# zero-o2-eliminator.net
KiCad netlist of a schematic drawn in EAGLE
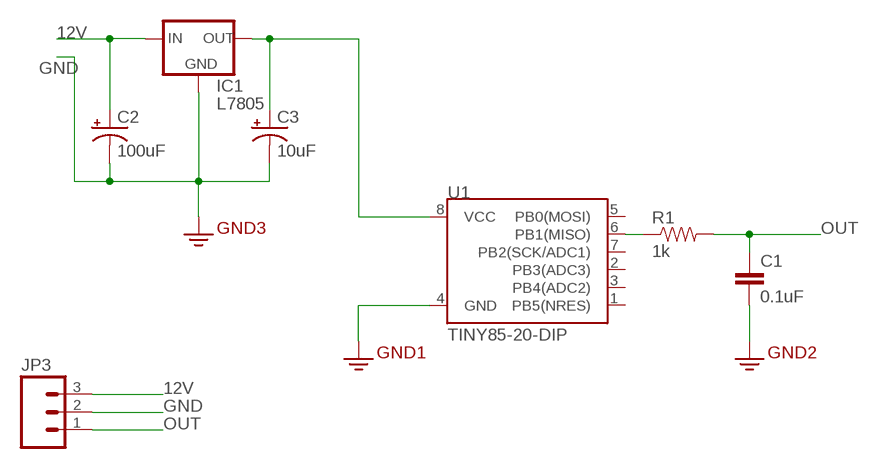
[diagram p0: schematic, sheet 1]

(export (version "E")
  (design (tool "Eeschema 10.0.6"))
  (components
    (comp (ref "C1")
      (value "0.1uF")
      (footprint "eagle-import:CAP-PTH-SMALL-KIT")
      (libsource (lib "eagle-import") (part "0.1UF-50V-20%(PTH)KIT-EZ"))
    )
    (comp (ref "C2")
      (value "100uF")
      (footprint "eagle-import:CPOL-RADIAL-10UF-25V-KIT")
      (libsource (lib "eagle-import") (part "10UF-25V-20%(PTH)KIT"))
    )
    (comp (ref "C3")
      (value "10uF")
      (footprint "eagle-import:CPOL-RADIAL-10UF-25V-KIT")
      (libsource (lib "eagle-import") (part "10UF-25V-20%(PTH)KIT"))
    )
    (comp (ref "IC1")
      (value "L7805")
      (footprint "eagle-import:78XXL")
      (libsource (lib "eagle-import") (part "V_REG_78XXSIDE"))
    )
    (comp (ref "JP3")
      (value "M03SCREW")
      (footprint "eagle-import:SCREWTERMINAL-3.5MM-3")
      (libsource (lib "eagle-import") (part "M03SCREW"))
    )
    (comp (ref "R1")
      (value "1k")
      (footprint "eagle-import:AXIAL-0.1EZ")
      (libsource (lib "eagle-import") (part "1KOHM-1/4W-5%(PTH)VERT-KIT"))
    )
    (comp (ref "U1")
      (value "TINY85-20-DIP")
      (footprint "eagle-import:DIP08")
      (libsource (lib "eagle-import") (part "ATTINY45TINY85-20-DIP"))
    )
  )
  (nets
    (net (code "1") (name "/12V") (class "Default")
      (node (ref "C2") (pin "1") (pinfunction "+_1") (pintype "passive"))
      (node (ref "IC1") (pin "IN") (pinfunction "IN_IN") (pintype "input"))
      (node (ref "JP3") (pin "3") (pinfunction "3_3") (pintype "passive"))
    )
    (net (code "2") (name "/OUT") (class "Default")
      (node (ref "C1") (pin "1") (pinfunction "1_1") (pintype "passive"))
      (node (ref "JP3") (pin "1") (pinfunction "1_1") (pintype "passive"))
      (node (ref "R1") (pin "P$2") (pinfunction "2_P$2") (pintype "passive"))
    )
    (net (code "3") (name "GND2") (class "Default")
      (node (ref "C1") (pin "2") (pinfunction "2_2") (pintype "passive"))
      (node (ref "C2") (pin "2") (pinfunction "-_2") (pintype "passive"))
      (node (ref "C3") (pin "2") (pinfunction "-_2") (pintype "passive"))
      (node (ref "IC1") (pin "GND") (pinfunction "GND_GND") (pintype "input"))
      (node (ref "JP3") (pin "2") (pinfunction "2_2") (pintype "passive"))
      (node (ref "U1") (pin "4") (pinfunction "GND_4") (pintype "bidirectional"))
    )
    (net (code "4") (name "Net-(C3-+)") (class "Default")
      (node (ref "C3") (pin "1") (pinfunction "+_1") (pintype "passive"))
      (node (ref "IC1") (pin "OUT") (pinfunction "OUT_OUT") (pintype "output"))
      (node (ref "U1") (pin "8") (pinfunction "VCC_8") (pintype "bidirectional"))
    )
    (net (code "5") (name "Net-(R1-1)") (class "Default")
      (node (ref "R1") (pin "P$1") (pinfunction "1_P$1") (pintype "passive"))
      (node (ref "U1") (pin "6") (pinfunction "PB1(MISO)_6") (pintype "bidirectional"))
    )
    (net (code "6") (name "unconnected-(U1-PB0(MOSI)-Pad5)") (class "Default")
      (node (ref "U1") (pin "5") (pinfunction "PB0(MOSI)_5") (pintype "bidirectional"))
    )
    (net (code "7") (name "unconnected-(U1-PB2(SCK{slash}ADC1)-Pad7)") (class "Default")
      (node (ref "U1") (pin "7") (pinfunction "PB2(SCK/ADC1)_7") (pintype "bidirectional"))
    )
    (net (code "8") (name "unconnected-(U1-PB3(ADC3)-Pad2)") (class "Default")
      (node (ref "U1") (pin "2") (pinfunction "PB3(ADC3)_2") (pintype "bidirectional"))
    )
    (net (code "9") (name "unconnected-(U1-PB4(ADC2)-Pad3)") (class "Default")
      (node (ref "U1") (pin "3") (pinfunction "PB4(ADC2)_3") (pintype "bidirectional"))
    )
    (net (code "10") (name "unconnected-(U1-PB5(NRES)-Pad1)") (class "Default")
      (node (ref "U1") (pin "1") (pinfunction "PB5(NRES)_1") (pintype "bidirectional"))
    )
  )
)
